# Dimer_Power_Board.net
KiCad netlist of a schematic drawn in Altium Designer
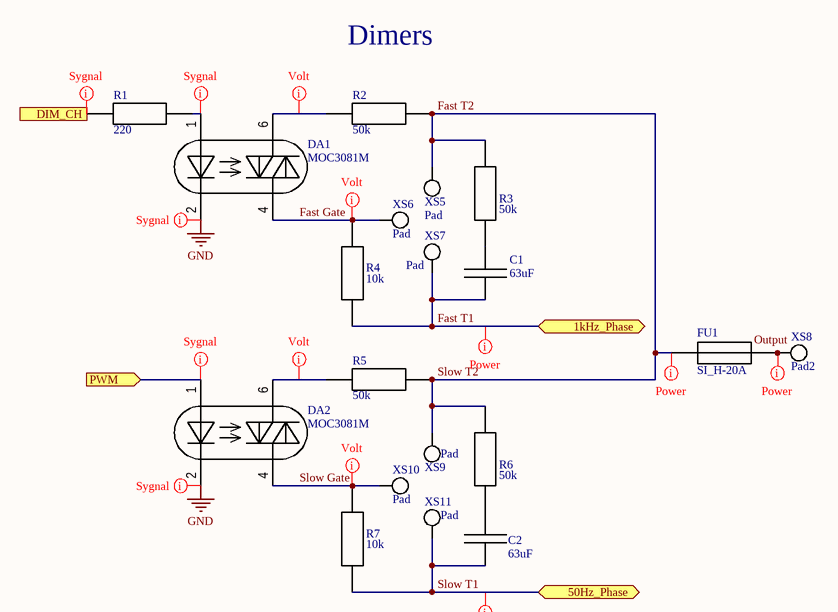
[diagram p0: Dimer_Power_Board.SchDoc]

(export (version "E")
  (design (tool "Eeschema 10.0.6"))
  (components
    (comp (ref "C1")
      (value "63uF")
      (footprint "C-15")
      (description "C_15")
      (libsource (lib "Nolden_Power_Board_V2") (part "C_15"))
    )
    (comp (ref "C2")
      (value "63uF")
      (footprint "C-15")
      (description "C_15")
      (libsource (lib "Nolden_Power_Board_V2") (part "C_15"))
    )
    (comp (ref "DA1")
      (value "MOC3081M")
      (footprint "DIL-06")
      (description "MOC3081M Optosimistor Driver")
      (libsource (lib "Nolden_Power_Board_V2") (part "MOC3081M"))
    )
    (comp (ref "DA2")
      (value "MOC3081M")
      (footprint "DIL-06")
      (description "MOC3081M Optosimistor Driver")
      (libsource (lib "Nolden_Power_Board_V2") (part "MOC3081M"))
    )
    (comp (ref "FU1")
      (value "SI_H-20A")
      (footprint "SI_H-20A_")
      (libsource (lib "Nolden_Power_Board_V2") (part "Fuse SI_H-20A"))
    )
    (comp (ref "R1")
      (value "220")
      (footprint "RESC2012X06N")
      (description "Resistor")
      (libsource (lib "Dimer") (part "220"))
    )
    (comp (ref "R2")
      (value "50k")
      (footprint "R-15")
      (description "Res_15")
      (libsource (lib "Nolden_Power_Board_V2") (part "Res_15"))
    )
    (comp (ref "R3")
      (value "50k")
      (footprint "R-15")
      (description "Res_15")
      (libsource (lib "Nolden_Power_Board_V2") (part "Res_15"))
    )
    (comp (ref "R4")
      (value "10k")
      (footprint "R-10")
      (description "Res_10")
      (libsource (lib "Nolden_Power_Board_V2") (part "Res_10"))
    )
    (comp (ref "R5")
      (value "50k")
      (footprint "R-15")
      (description "Res_15")
      (libsource (lib "Nolden_Power_Board_V2") (part "Res_15"))
    )
    (comp (ref "R6")
      (value "50k")
      (footprint "R-15")
      (description "Res_15")
      (libsource (lib "Nolden_Power_Board_V2") (part "Res_15"))
    )
    (comp (ref "R7")
      (value "10k")
      (footprint "R-10")
      (description "Res_10")
      (libsource (lib "Nolden_Power_Board_V2") (part "Res_10"))
    )
    (comp (ref "XS5")
      (value "Pad")
      (footprint "LOTPAD")
      (description "PCB TH Pad")
      (libsource (lib "Nolden_Power_Board_V2") (part "Pad"))
    )
    (comp (ref "XS6")
      (value "Pad")
      (footprint "LOTPAD")
      (description "PCB TH Pad")
      (libsource (lib "Nolden_Power_Board_V2") (part "Pad"))
    )
    (comp (ref "XS7")
      (value "Pad")
      (footprint "LOTPAD")
      (description "PCB TH Pad")
      (libsource (lib "Nolden_Power_Board_V2") (part "Pad"))
    )
    (comp (ref "XS8")
      (value "Pad2")
      (footprint "LOTPAD_2")
      (description "PCB TH Pad")
      (libsource (lib "Nolden_Power_Board_V2") (part "Pad2"))
    )
    (comp (ref "XS9")
      (value "Pad")
      (footprint "LOTPAD")
      (description "PCB TH Pad")
      (libsource (lib "Nolden_Power_Board_V2") (part "Pad"))
    )
    (comp (ref "XS10")
      (value "Pad")
      (footprint "LOTPAD")
      (description "PCB TH Pad")
      (libsource (lib "Nolden_Power_Board_V2") (part "Pad"))
    )
    (comp (ref "XS11")
      (value "Pad")
      (footprint "LOTPAD")
      (description "PCB TH Pad")
      (libsource (lib "Nolden_Power_Board_V2") (part "Pad"))
    )
  )
  (nets
    (net (code "1") (name "/DIM_CH") (class "Default")
      (node (ref "R1") (pin "1") (pinfunction "1_1") (pintype "passive"))
    )
    (net (code "2") (name "/Fast Gate") (class "Default")
      (node (ref "DA1") (pin "4") (pinfunction "Main_terminal_4") (pintype "power_in"))
      (node (ref "R4") (pin "2") (pinfunction "2_2") (pintype "passive"))
      (node (ref "XS6") (pin "1") (pinfunction "1_1") (pintype "passive"))
    )
    (net (code "3") (name "/Fast T1") (class "Default")
      (node (ref "C1") (pin "1") (pinfunction "1_1") (pintype "passive"))
      (node (ref "R4") (pin "1") (pinfunction "1_1") (pintype "passive"))
      (node (ref "XS7") (pin "1") (pinfunction "1_1") (pintype "passive"))
    )
    (net (code "4") (name "/Fast T2") (class "Default")
      (node (ref "FU1") (pin "3") (pinfunction "3_3") (pintype "passive"))
      (node (ref "R2") (pin "2") (pinfunction "2_2") (pintype "passive"))
      (node (ref "R3") (pin "2") (pinfunction "2_2") (pintype "passive"))
      (node (ref "R5") (pin "2") (pinfunction "2_2") (pintype "passive"))
      (node (ref "R6") (pin "2") (pinfunction "2_2") (pintype "passive"))
      (node (ref "XS5") (pin "1") (pinfunction "1_1") (pintype "passive"))
      (node (ref "XS9") (pin "1") (pinfunction "1_1") (pintype "passive"))
    )
    (net (code "6") (name "/PWM") (class "Default")
      (node (ref "DA2") (pin "1") (pinfunction "Anode_1") (pintype "passive"))
    )
    (net (code "7") (name "/Slow Gate") (class "Default")
      (node (ref "DA2") (pin "4") (pinfunction "Main_terminal_4") (pintype "power_in"))
      (node (ref "R7") (pin "2") (pinfunction "2_2") (pintype "passive"))
      (node (ref "XS10") (pin "1") (pinfunction "1_1") (pintype "passive"))
    )
    (net (code "8") (name "/Slow T1") (class "Default")
      (node (ref "C2") (pin "1") (pinfunction "1_1") (pintype "passive"))
      (node (ref "R7") (pin "1") (pinfunction "1_1") (pintype "passive"))
      (node (ref "XS11") (pin "1") (pinfunction "1_1") (pintype "passive"))
    )
    (net (code "9") (name "GND") (class "Default")
      (node (ref "DA1") (pin "2") (pinfunction "Cathode_2") (pintype "passive"))
      (node (ref "DA2") (pin "2") (pinfunction "Cathode_2") (pintype "passive"))
    )
    (net (code "10") (name "Net-(C1-Pad2)") (class "Default")
      (node (ref "C1") (pin "2") (pinfunction "2_2") (pintype "passive"))
      (node (ref "R3") (pin "1") (pinfunction "1_1") (pintype "passive"))
    )
    (net (code "11") (name "Net-(C2-Pad2)") (class "Default")
      (node (ref "C2") (pin "2") (pinfunction "2_2") (pintype "passive"))
      (node (ref "R6") (pin "1") (pinfunction "1_1") (pintype "passive"))
    )
    (net (code "12") (name "Net-(DA1-Anode)") (class "Default")
      (node (ref "DA1") (pin "1") (pinfunction "Anode_1") (pintype "passive"))
      (node (ref "R1") (pin "2") (pinfunction "2_2") (pintype "passive"))
    )
    (net (code "13") (name "Net-(DA1-Main_terminal-Pad6)") (class "Default")
      (node (ref "DA1") (pin "6") (pinfunction "Main_terminal_6") (pintype "power_in"))
      (node (ref "R2") (pin "1") (pinfunction "1_1") (pintype "passive"))
    )
    (net (code "14") (name "Net-(DA2-Main_terminal-Pad6)") (class "Default")
      (node (ref "DA2") (pin "6") (pinfunction "Main_terminal_6") (pintype "power_in"))
      (node (ref "R5") (pin "1") (pinfunction "1_1") (pintype "passive"))
    )
    (net (code "15") (name "Net-(FU1-Pad2)") (class "Default")
      (node (ref "FU1") (pin "2") (pinfunction "2_2") (pintype "passive"))
      (node (ref "XS8") (pin "1") (pinfunction "1_1") (pintype "passive"))
      (node (ref "XS8") (pin "2") (pinfunction "2_2") (pintype "passive"))
    )
  )
)
